# domino4_EPA.net
KiCad netlist of a schematic drawn in EAGLE
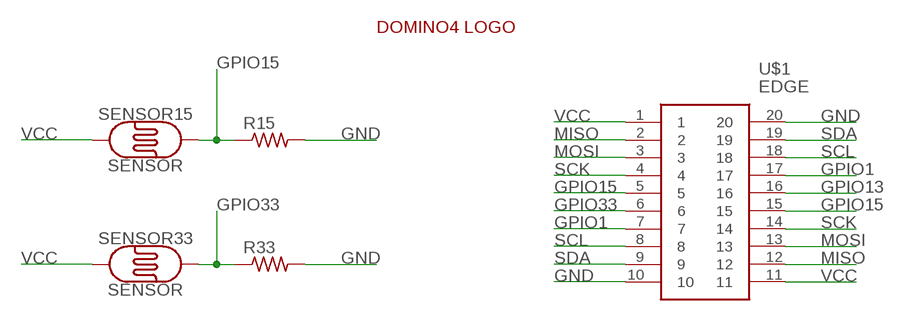
[diagram p0: schematic, sheet 1]

(export (version "E")
  (design (tool "Eeschema 10.0.6"))
  (components
    (comp (ref "R15")
      (value "R-US_FLIPFLOP")
      (footprint "eagle-import:0805-THM")
      (libsource (lib "eagle-import") (part "R-US_FLIPFLOP"))
    )
    (comp (ref "R33")
      (value "R-US_FLIPFLOP")
      (footprint "eagle-import:0805-THM")
      (libsource (lib "eagle-import") (part "R-US_FLIPFLOP"))
    )
    (comp (ref "SENSOR15")
      (value "SENSOR")
      (footprint "eagle-import:PHOTOCELL-KIT")
      (libsource (lib "eagle-import") (part "PHOTOCELLPTH-KIT"))
    )
    (comp (ref "SENSOR33")
      (value "SENSOR")
      (footprint "eagle-import:PHOTOCELL-KIT")
      (libsource (lib "eagle-import") (part "PHOTOCELLPTH-KIT"))
    )
    (comp (ref "U$1")
      (value "EDGE")
      (footprint "eagle-import:EDGE")
      (libsource (lib "eagle-import") (part "EDGE"))
    )
    (comp (ref "U$5")
      (value "DOMINO4_LOGO")
      (footprint "eagle-import:DOMINO4_LOGO")
      (libsource (lib "eagle-import") (part "DOMINO4_LOGO"))
    )
  )
  (nets
    (net (code "1") (name "/GND") (class "Default")
      (node (ref "R15") (pin "2") (pinfunction "2_2") (pintype "passive"))
      (node (ref "R33") (pin "2") (pinfunction "2_2") (pintype "passive"))
      (node (ref "U$1") (pin "10") (pinfunction "10_10") (pintype "bidirectional"))
      (node (ref "U$1") (pin "20") (pinfunction "20_20") (pintype "bidirectional"))
    )
    (net (code "2") (name "/GPIO1") (class "Default")
      (node (ref "U$1") (pin "17") (pinfunction "17_17") (pintype "bidirectional"))
      (node (ref "U$1") (pin "7") (pinfunction "7_7") (pintype "bidirectional"))
    )
    (net (code "3") (name "/GPIO13") (class "Default")
      (node (ref "U$1") (pin "16") (pinfunction "16_16") (pintype "bidirectional"))
    )
    (net (code "4") (name "/GPIO15") (class "Default")
      (node (ref "R15") (pin "1") (pinfunction "1_1") (pintype "passive"))
      (node (ref "SENSOR15") (pin "2") (pinfunction "P$2_2") (pintype "bidirectional"))
      (node (ref "U$1") (pin "15") (pinfunction "15_15") (pintype "bidirectional"))
      (node (ref "U$1") (pin "5") (pinfunction "5_5") (pintype "bidirectional"))
    )
    (net (code "5") (name "/GPIO33") (class "Default")
      (node (ref "R33") (pin "1") (pinfunction "1_1") (pintype "passive"))
      (node (ref "SENSOR33") (pin "2") (pinfunction "P$2_2") (pintype "bidirectional"))
      (node (ref "U$1") (pin "6") (pinfunction "6_6") (pintype "bidirectional"))
    )
    (net (code "6") (name "/MISO") (class "Default")
      (node (ref "U$1") (pin "12") (pinfunction "12_12") (pintype "bidirectional"))
      (node (ref "U$1") (pin "2") (pinfunction "2_2") (pintype "bidirectional"))
    )
    (net (code "7") (name "/MOSI") (class "Default")
      (node (ref "U$1") (pin "13") (pinfunction "13_13") (pintype "bidirectional"))
      (node (ref "U$1") (pin "3") (pinfunction "3_3") (pintype "bidirectional"))
    )
    (net (code "8") (name "/SCK") (class "Default")
      (node (ref "U$1") (pin "14") (pinfunction "14_14") (pintype "bidirectional"))
      (node (ref "U$1") (pin "4") (pinfunction "4_4") (pintype "bidirectional"))
    )
    (net (code "9") (name "/SCL") (class "Default")
      (node (ref "U$1") (pin "18") (pinfunction "18_18") (pintype "bidirectional"))
      (node (ref "U$1") (pin "8") (pinfunction "8_8") (pintype "bidirectional"))
    )
    (net (code "10") (name "/SDA") (class "Default")
      (node (ref "U$1") (pin "19") (pinfunction "19_19") (pintype "bidirectional"))
      (node (ref "U$1") (pin "9") (pinfunction "9_9") (pintype "bidirectional"))
    )
    (net (code "11") (name "/VCC") (class "Default")
      (node (ref "SENSOR15") (pin "1") (pinfunction "P$1_1") (pintype "bidirectional"))
      (node (ref "SENSOR33") (pin "1") (pinfunction "P$1_1") (pintype "bidirectional"))
      (node (ref "U$1") (pin "1") (pinfunction "1_1") (pintype "bidirectional"))
      (node (ref "U$1") (pin "11") (pinfunction "11_11") (pintype "bidirectional"))
    )
  )
)
